# T_STorM32_NT_motor_v42ECg4_000.net
KiCad netlist of a schematic drawn in EAGLE
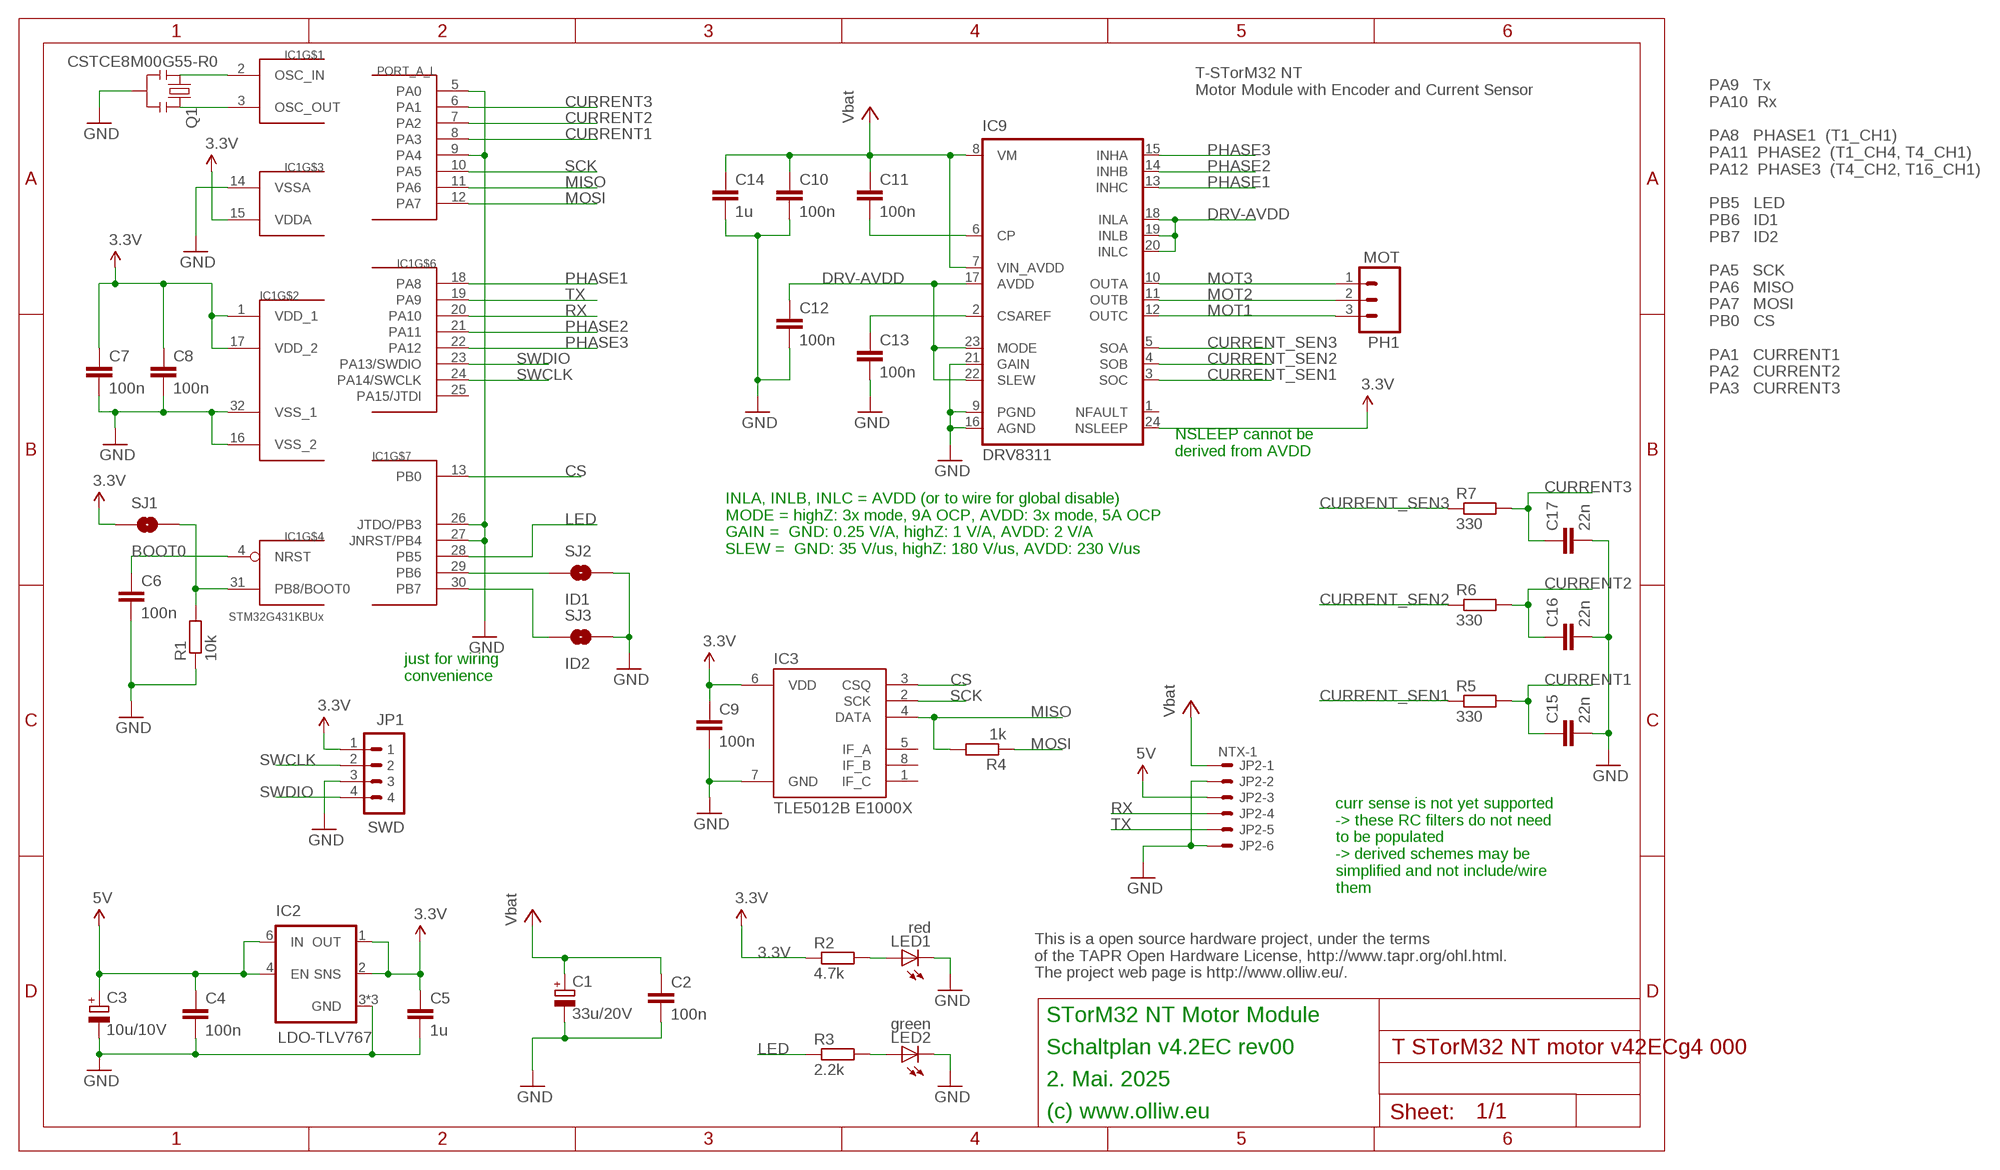
[diagram p0: schematic, sheet 1]

(export (version "E")
  (design (tool "Eeschema 10.0.6"))
  (components
    (comp (ref "C1")
      (value "33u/20V")
      (footprint "eagle-import:SMC_C")
      (libsource (lib "eagle-import") (part "CPOL-EUSMCC"))
    )
    (comp (ref "C2")
      (value "100n")
      (footprint "eagle-import:C0603")
      (libsource (lib "eagle-import") (part "C-EUC0603"))
    )
    (comp (ref "C3")
      (value "10u/10V")
      (footprint "eagle-import:SMC_B")
      (libsource (lib "eagle-import") (part "CPOL-EUSMCB"))
    )
    (comp (ref "C4")
      (value "100n")
      (footprint "eagle-import:C0603")
      (libsource (lib "eagle-import") (part "C-EUC0603"))
    )
    (comp (ref "C5")
      (value "1u")
      (footprint "eagle-import:C0603")
      (libsource (lib "eagle-import") (part "C-EUC0603"))
    )
    (comp (ref "C6")
      (value "100n")
      (footprint "eagle-import:C0402")
      (libsource (lib "eagle-import") (part "C-EUC0402"))
    )
    (comp (ref "C7")
      (value "100n")
      (footprint "eagle-import:C0402")
      (libsource (lib "eagle-import") (part "C-EUC0402"))
    )
    (comp (ref "C8")
      (value "100n")
      (footprint "eagle-import:C0402")
      (libsource (lib "eagle-import") (part "C-EUC0402"))
    )
    (comp (ref "C9")
      (value "100n")
      (footprint "eagle-import:C0402")
      (libsource (lib "eagle-import") (part "C-EUC0402"))
    )
    (comp (ref "C10")
      (value "100n")
      (footprint "eagle-import:C0402")
      (libsource (lib "eagle-import") (part "C-EUC0402"))
    )
    (comp (ref "C11")
      (value "100n")
      (footprint "eagle-import:C0402")
      (libsource (lib "eagle-import") (part "C-EUC0402"))
    )
    (comp (ref "C12")
      (value "100n")
      (footprint "eagle-import:C0402")
      (libsource (lib "eagle-import") (part "C-EUC0402"))
    )
    (comp (ref "C13")
      (value "100n")
      (footprint "eagle-import:C0402")
      (libsource (lib "eagle-import") (part "C-EUC0402"))
    )
    (comp (ref "C14")
      (value "1u")
      (footprint "eagle-import:C0603")
      (libsource (lib "eagle-import") (part "C-EUC0603"))
    )
    (comp (ref "C15")
      (value "22n")
      (footprint "eagle-import:C0402")
      (libsource (lib "eagle-import") (part "C-EUC0402"))
    )
    (comp (ref "C16")
      (value "22n")
      (footprint "eagle-import:C0402")
      (libsource (lib "eagle-import") (part "C-EUC0402"))
    )
    (comp (ref "C17")
      (value "22n")
      (footprint "eagle-import:C0402")
      (libsource (lib "eagle-import") (part "C-EUC0402"))
    )
    (comp (ref "IC1")
      (value "STM32G431KBUx")
      (footprint "eagle-import:UFQFPN32")
      (libsource (lib "eagle-import") (part "STM32G4X1KX"))
    )
    (comp (ref "IC2")
      (value "LDO-TLV767")
      (footprint "eagle-import:WSON-6-2X2")
      (libsource (lib "eagle-import") (part "LDO-TLV767"))
    )
    (comp (ref "IC3")
      (value "TLE5012B E1000X")
      (footprint "eagle-import:SO08")
      (libsource (lib "eagle-import") (part "TLE5012B"))
    )
    (comp (ref "IC9")
      (value "DRV8311")
      (footprint "eagle-import:QFN(WQFN)24-3X3-DRV8311")
      (libsource (lib "eagle-import") (part "DRV8311"))
    )
    (comp (ref "JP1")
      (value "SWD")
      (footprint "eagle-import:4X1_1P27_OCT_BILEX")
      (libsource (lib "eagle-import") (part "P4X1_1P27-OCT_BILEX"))
    )
    (comp (ref "JP2")
      (value "NTX-1")
      (footprint "eagle-import:SM06B-SRSS-TB")
      (libsource (lib "eagle-import") (part "?M06B-SRSS-TBS"))
    )
    (comp (ref "LED1")
      (value "red")
      (footprint "eagle-import:CHIPLED_0603")
      (libsource (lib "eagle-import") (part "LEDCHIPLED_0603"))
    )
    (comp (ref "LED2")
      (value "green")
      (footprint "eagle-import:CHIPLED_0603")
      (libsource (lib "eagle-import") (part "LEDCHIPLED_0603"))
    )
    (comp (ref "PH1")
      (value "MOT")
      (footprint "eagle-import:1X03_NO_SILK")
      (libsource (lib "eagle-import") (part "M031X03_NO_SILK"))
    )
    (comp (ref "Q1")
      (value "CSTCE8M00G55-R0")
      (footprint "eagle-import:RESONATOR-SMD")
      (libsource (lib "eagle-import") (part "RESONATORSMD"))
    )
    (comp (ref "R1")
      (value "10k")
      (footprint "eagle-import:R0402")
      (libsource (lib "eagle-import") (part "R-EU_R0402"))
    )
    (comp (ref "R2")
      (value "4.7k")
      (footprint "eagle-import:R0402")
      (libsource (lib "eagle-import") (part "R-EU_R0402"))
    )
    (comp (ref "R3")
      (value "2.2k")
      (footprint "eagle-import:R0402")
      (libsource (lib "eagle-import") (part "R-EU_R0402"))
    )
    (comp (ref "R4")
      (value "1k")
      (footprint "eagle-import:R0402")
      (libsource (lib "eagle-import") (part "R-EU_R0402"))
    )
    (comp (ref "R5")
      (value "330")
      (footprint "eagle-import:R0402")
      (libsource (lib "eagle-import") (part "R-EU_R0402"))
    )
    (comp (ref "R6")
      (value "330")
      (footprint "eagle-import:R0402")
      (libsource (lib "eagle-import") (part "R-EU_R0402"))
    )
    (comp (ref "R7")
      (value "330")
      (footprint "eagle-import:R0402")
      (libsource (lib "eagle-import") (part "R-EU_R0402"))
    )
    (comp (ref "SJ1")
      (value "BOOT0")
      (footprint "eagle-import:SJ_2S-NO")
      (libsource (lib "eagle-import") (part "SOLDERJUMPERNO"))
    )
    (comp (ref "SJ2")
      (value "ID1")
      (footprint "eagle-import:SJ_2S-NO")
      (libsource (lib "eagle-import") (part "SOLDERJUMPERNO"))
    )
    (comp (ref "SJ3")
      (value "ID2")
      (footprint "eagle-import:SJ_2S-NO")
      (libsource (lib "eagle-import") (part "SOLDERJUMPERNO"))
    )
  )
  (nets
    (net (code "1") (name "/CS") (class "Default")
      (node (ref "IC1") (pin "13") (pinfunction "PB0_13") (pintype "bidirectional"))
      (node (ref "IC3") (pin "3") (pinfunction "CSQ_3") (pintype "input"))
    )
    (net (code "2") (name "/CURRENT1") (class "Default")
      (node (ref "C15") (pin "1") (pinfunction "1_1") (pintype "passive"))
      (node (ref "IC1") (pin "8") (pinfunction "PA3_8") (pintype "bidirectional"))
      (node (ref "R5") (pin "2") (pinfunction "2_2") (pintype "passive"))
    )
    (net (code "3") (name "/CURRENT2") (class "Default")
      (node (ref "C16") (pin "1") (pinfunction "1_1") (pintype "passive"))
      (node (ref "IC1") (pin "7") (pinfunction "PA2_7") (pintype "bidirectional"))
      (node (ref "R6") (pin "2") (pinfunction "2_2") (pintype "passive"))
    )
    (net (code "4") (name "/CURRENT3") (class "Default")
      (node (ref "C17") (pin "1") (pinfunction "1_1") (pintype "passive"))
      (node (ref "IC1") (pin "6") (pinfunction "PA1_6") (pintype "bidirectional"))
      (node (ref "R7") (pin "2") (pinfunction "2_2") (pintype "passive"))
    )
    (net (code "5") (name "/CURRENT_SEN1") (class "Default")
      (node (ref "IC9") (pin "3") (pinfunction "SOC_3") (pintype "output"))
      (node (ref "R5") (pin "1") (pinfunction "1_1") (pintype "passive"))
    )
    (net (code "6") (name "/CURRENT_SEN2") (class "Default")
      (node (ref "IC9") (pin "4") (pinfunction "SOB_4") (pintype "output"))
      (node (ref "R6") (pin "1") (pinfunction "1_1") (pintype "passive"))
    )
    (net (code "7") (name "/CURRENT_SEN3") (class "Default")
      (node (ref "IC9") (pin "5") (pinfunction "SOA_5") (pintype "output"))
      (node (ref "R7") (pin "1") (pinfunction "1_1") (pintype "passive"))
    )
    (net (code "8") (name "/DRV-AVDD") (class "Default")
      (node (ref "C12") (pin "1") (pinfunction "1_1") (pintype "passive"))
      (node (ref "IC9") (pin "17") (pinfunction "AVDD_17") (pintype "power_in"))
      (node (ref "IC9") (pin "18") (pinfunction "INLA_18") (pintype "input"))
      (node (ref "IC9") (pin "19") (pinfunction "INLB_19") (pintype "input"))
      (node (ref "IC9") (pin "20") (pinfunction "INLC_20") (pintype "input"))
      (node (ref "IC9") (pin "22") (pinfunction "SLEW_22") (pintype "input"))
      (node (ref "IC9") (pin "23") (pinfunction "MODE_23") (pintype "input"))
    )
    (net (code "9") (name "/LED") (class "Default")
      (node (ref "IC1") (pin "28") (pinfunction "PB5_28") (pintype "bidirectional"))
      (node (ref "R3") (pin "1") (pinfunction "1_1") (pintype "passive"))
    )
    (net (code "10") (name "/MISO") (class "Default")
      (node (ref "IC1") (pin "11") (pinfunction "PA6_11") (pintype "bidirectional"))
      (node (ref "IC3") (pin "4") (pinfunction "DATA_4") (pintype "bidirectional"))
      (node (ref "R4") (pin "2") (pinfunction "2_2") (pintype "passive"))
    )
    (net (code "11") (name "/MOSI") (class "Default")
      (node (ref "IC1") (pin "12") (pinfunction "PA7_12") (pintype "bidirectional"))
      (node (ref "R4") (pin "1") (pinfunction "1_1") (pintype "passive"))
    )
    (net (code "12") (name "/MOT1") (class "Default")
      (node (ref "IC9") (pin "12") (pinfunction "OUTC_12") (pintype "output"))
      (node (ref "PH1") (pin "3") (pinfunction "3_3") (pintype "passive"))
    )
    (net (code "13") (name "/MOT2") (class "Default")
      (node (ref "IC9") (pin "11") (pinfunction "OUTB_11") (pintype "output"))
      (node (ref "PH1") (pin "2") (pinfunction "2_2") (pintype "passive"))
    )
    (net (code "14") (name "/MOT3") (class "Default")
      (node (ref "IC9") (pin "10") (pinfunction "OUTA_10") (pintype "output"))
      (node (ref "PH1") (pin "1") (pinfunction "1_1") (pintype "passive"))
    )
    (net (code "15") (name "/PHASE1") (class "Default")
      (node (ref "IC1") (pin "18") (pinfunction "PA8_18") (pintype "bidirectional"))
      (node (ref "IC9") (pin "13") (pinfunction "INHC_13") (pintype "input"))
    )
    (net (code "16") (name "/PHASE2") (class "Default")
      (node (ref "IC1") (pin "21") (pinfunction "PA11_21") (pintype "bidirectional"))
      (node (ref "IC9") (pin "14") (pinfunction "INHB_14") (pintype "input"))
    )
    (net (code "17") (name "/PHASE3") (class "Default")
      (node (ref "IC1") (pin "22") (pinfunction "PA12_22") (pintype "bidirectional"))
      (node (ref "IC9") (pin "15") (pinfunction "INHA_15") (pintype "input"))
    )
    (net (code "18") (name "/RX") (class "Default")
      (node (ref "IC1") (pin "20") (pinfunction "PA10_20") (pintype "bidirectional"))
      (node (ref "JP2") (pin "4") (pinfunction "S_4") (pintype "passive"))
    )
    (net (code "19") (name "/SCK") (class "Default")
      (node (ref "IC1") (pin "10") (pinfunction "PA5_10") (pintype "bidirectional"))
      (node (ref "IC3") (pin "2") (pinfunction "SCK_2") (pintype "input"))
    )
    (net (code "20") (name "/SWCLK") (class "Default")
      (node (ref "IC1") (pin "24") (pinfunction "PA14/SWCLK_24") (pintype "bidirectional"))
      (node (ref "JP1") (pin "2") (pinfunction "2_2") (pintype "passive"))
    )
    (net (code "21") (name "/SWDIO") (class "Default")
      (node (ref "IC1") (pin "23") (pinfunction "PA13/SWDIO_23") (pintype "bidirectional"))
      (node (ref "JP1") (pin "4") (pinfunction "4_4") (pintype "passive"))
    )
    (net (code "22") (name "/TX") (class "Default")
      (node (ref "IC1") (pin "19") (pinfunction "PA9_19") (pintype "bidirectional"))
      (node (ref "JP2") (pin "5") (pinfunction "S_5") (pintype "passive"))
    )
    (net (code "23") (name "3.3V") (class "Default")
      (node (ref "C5") (pin "1") (pinfunction "1_1") (pintype "passive"))
      (node (ref "C7") (pin "1") (pinfunction "1_1") (pintype "passive"))
      (node (ref "C8") (pin "1") (pinfunction "1_1") (pintype "passive"))
      (node (ref "C9") (pin "1") (pinfunction "1_1") (pintype "passive"))
      (node (ref "IC1") (pin "1") (pinfunction "VDD_1_1") (pintype "power_in"))
      (node (ref "IC1") (pin "15") (pinfunction "VDDA_15") (pintype "power_in"))
      (node (ref "IC1") (pin "17") (pinfunction "VDD_2_17") (pintype "power_in"))
      (node (ref "IC2") (pin "1") (pinfunction "OUT_1") (pintype "output"))
      (node (ref "IC2") (pin "2") (pinfunction "SNS_2") (pintype "input"))
      (node (ref "IC3") (pin "6") (pinfunction "VDD_6") (pintype "power_in"))
      (node (ref "IC9") (pin "24") (pinfunction "NSLEEP_24") (pintype "input"))
      (node (ref "JP1") (pin "1") (pinfunction "1_1") (pintype "passive"))
      (node (ref "R2") (pin "1") (pinfunction "1_1") (pintype "passive"))
      (node (ref "SJ1") (pin "1") (pinfunction "1_1") (pintype "passive"))
    )
    (net (code "24") (name "5V") (class "Default")
      (node (ref "C3") (pin "+") (pinfunction "+_+") (pintype "passive"))
      (node (ref "C4") (pin "1") (pinfunction "1_1") (pintype "passive"))
      (node (ref "IC2") (pin "4") (pinfunction "EN_4") (pintype "input"))
      (node (ref "IC2") (pin "6") (pinfunction "IN_6") (pintype "power_in"))
      (node (ref "JP2") (pin "3") (pinfunction "S_3") (pintype "passive"))
    )
    (net (code "25") (name "GND") (class "Default")
      (node (ref "C1") (pin "-") (pinfunction "-_-") (pintype "passive"))
      (node (ref "C10") (pin "2") (pinfunction "2_2") (pintype "passive"))
      (node (ref "C12") (pin "2") (pinfunction "2_2") (pintype "passive"))
      (node (ref "C13") (pin "2") (pinfunction "2_2") (pintype "passive"))
      (node (ref "C14") (pin "2") (pinfunction "2_2") (pintype "passive"))
      (node (ref "C15") (pin "2") (pinfunction "2_2") (pintype "passive"))
      (node (ref "C16") (pin "2") (pinfunction "2_2") (pintype "passive"))
      (node (ref "C17") (pin "2") (pinfunction "2_2") (pintype "passive"))
      (node (ref "C2") (pin "2") (pinfunction "2_2") (pintype "passive"))
      (node (ref "C3") (pin "-") (pinfunction "-_-") (pintype "passive"))
      (node (ref "C4") (pin "2") (pinfunction "2_2") (pintype "passive"))
      (node (ref "C5") (pin "2") (pinfunction "2_2") (pintype "passive"))
      (node (ref "C6") (pin "2") (pinfunction "2_2") (pintype "passive"))
      (node (ref "C7") (pin "2") (pinfunction "2_2") (pintype "passive"))
      (node (ref "C8") (pin "2") (pinfunction "2_2") (pintype "passive"))
      (node (ref "C9") (pin "2") (pinfunction "2_2") (pintype "passive"))
      (node (ref "IC1") (pin "14") (pinfunction "VSSA_14") (pintype "power_in"))
      (node (ref "IC1") (pin "16") (pinfunction "VSS_2_16") (pintype "power_in"))
      (node (ref "IC1") (pin "26") (pinfunction "JTDO/PB3_26") (pintype "bidirectional"))
      (node (ref "IC1") (pin "27") (pinfunction "JNRST/PB4_27") (pintype "bidirectional"))
      (node (ref "IC1") (pin "32") (pinfunction "VSS_1_32") (pintype "power_in"))
      (node (ref "IC1") (pin "5") (pinfunction "PA0_5") (pintype "bidirectional"))
      (node (ref "IC1") (pin "9") (pinfunction "PA4_9") (pintype "bidirectional"))
      (node (ref "IC2") (pin "3") (pinfunction "GND_3") (pintype "power_in"))
      (node (ref "IC2") (pin "5") (pinfunction "GND_5") (pintype "power_in"))
      (node (ref "IC2") (pin "7") (pinfunction "GND_7") (pintype "power_in"))
      (node (ref "IC3") (pin "7") (pinfunction "GND_7") (pintype "power_in"))
      (node (ref "IC9") (pin "16") (pinfunction "AGND_16") (pintype "power_in"))
      (node (ref "IC9") (pin "21") (pinfunction "GAIN_21") (pintype "input"))
      (node (ref "IC9") (pin "9") (pinfunction "PGND_9") (pintype "power_in"))
      (node (ref "JP1") (pin "3") (pinfunction "3_3") (pintype "passive"))
      (node (ref "JP2") (pin "2") (pinfunction "S_2") (pintype "passive"))
      (node (ref "JP2") (pin "6") (pinfunction "S_6") (pintype "passive"))
      (node (ref "LED1") (pin "C") (pinfunction "C_C") (pintype "passive"))
      (node (ref "LED2") (pin "C") (pinfunction "C_C") (pintype "passive"))
      (node (ref "Q1") (pin "2") (pinfunction "2_2") (pintype "passive"))
      (node (ref "R1") (pin "1") (pinfunction "1_1") (pintype "passive"))
      (node (ref "SJ2") (pin "2") (pinfunction "2_2") (pintype "passive"))
      (node (ref "SJ3") (pin "2") (pinfunction "2_2") (pintype "passive"))
    )
    (net (code "26") (name "Net-(IC1A-OSC_IN)") (class "Default")
      (node (ref "IC1") (pin "2") (pinfunction "OSC_IN_2") (pintype "input"))
      (node (ref "Q1") (pin "1") (pinfunction "1_1") (pintype "passive"))
    )
    (net (code "27") (name "Net-(IC1A-OSC_OUT)") (class "Default")
      (node (ref "IC1") (pin "3") (pinfunction "OSC_OUT_3") (pintype "output"))
      (node (ref "Q1") (pin "3") (pinfunction "3_3") (pintype "passive"))
    )
    (net (code "28") (name "Net-(IC1D-NRST)") (class "Default")
      (node (ref "C6") (pin "1") (pinfunction "1_1") (pintype "passive"))
      (node (ref "IC1") (pin "4") (pinfunction "NRST_4") (pintype "input"))
    )
    (net (code "29") (name "Net-(IC1D-PB8{slash}BOOT0)") (class "Default")
      (node (ref "IC1") (pin "31") (pinfunction "PB8/BOOT0_31") (pintype "input"))
      (node (ref "R1") (pin "2") (pinfunction "2_2") (pintype "passive"))
      (node (ref "SJ1") (pin "2") (pinfunction "2_2") (pintype "passive"))
    )
    (net (code "30") (name "Net-(IC1G-PB6)") (class "Default")
      (node (ref "IC1") (pin "29") (pinfunction "PB6_29") (pintype "bidirectional"))
      (node (ref "SJ2") (pin "1") (pinfunction "1_1") (pintype "passive"))
    )
    (net (code "31") (name "Net-(IC1G-PB7)") (class "Default")
      (node (ref "IC1") (pin "30") (pinfunction "PB7_30") (pintype "bidirectional"))
      (node (ref "SJ3") (pin "1") (pinfunction "1_1") (pintype "passive"))
    )
    (net (code "32") (name "Net-(IC9-CP)") (class "Default")
      (node (ref "C11") (pin "2") (pinfunction "2_2") (pintype "passive"))
      (node (ref "IC9") (pin "6") (pinfunction "CP_6") (pintype "power_in"))
    )
    (net (code "33") (name "Net-(IC9-CSAREF)") (class "Default")
      (node (ref "C13") (pin "1") (pinfunction "1_1") (pintype "passive"))
      (node (ref "IC9") (pin "2") (pinfunction "CSAREF_2") (pintype "power_in"))
    )
    (net (code "34") (name "Net-(LED1-PadA)") (class "Default")
      (node (ref "LED1") (pin "A") (pinfunction "A_A") (pintype "passive"))
      (node (ref "R2") (pin "2") (pinfunction "2_2") (pintype "passive"))
    )
    (net (code "35") (name "Net-(LED2-PadA)") (class "Default")
      (node (ref "LED2") (pin "A") (pinfunction "A_A") (pintype "passive"))
      (node (ref "R3") (pin "2") (pinfunction "2_2") (pintype "passive"))
    )
    (net (code "36") (name "Vbat") (class "Default")
      (node (ref "C1") (pin "+") (pinfunction "+_+") (pintype "passive"))
      (node (ref "C10") (pin "1") (pinfunction "1_1") (pintype "passive"))
      (node (ref "C11") (pin "1") (pinfunction "1_1") (pintype "passive"))
      (node (ref "C14") (pin "1") (pinfunction "1_1") (pintype "passive"))
      (node (ref "C2") (pin "1") (pinfunction "1_1") (pintype "passive"))
      (node (ref "IC9") (pin "7") (pinfunction "VIN_AVDD_7") (pintype "power_in"))
      (node (ref "IC9") (pin "8") (pinfunction "VM_8") (pintype "power_in"))
      (node (ref "JP2") (pin "1") (pinfunction "S_1") (pintype "passive"))
    )
    (net (code "37") (name "unconnected-(IC1F-PA15{slash}JTDI-Pad25)") (class "Default")
      (node (ref "IC1") (pin "25") (pinfunction "PA15/JTDI_25") (pintype "bidirectional"))
    )
    (net (code "38") (name "unconnected-(IC3-IF_A-Pad5)") (class "Default")
      (node (ref "IC3") (pin "5") (pinfunction "IF_A_5") (pintype "bidirectional"))
    )
    (net (code "39") (name "unconnected-(IC3-IF_B-Pad8)") (class "Default")
      (node (ref "IC3") (pin "8") (pinfunction "IF_B_8") (pintype "output"))
    )
    (net (code "40") (name "unconnected-(IC3-IF_C-Pad1)") (class "Default")
      (node (ref "IC3") (pin "1") (pinfunction "IF_C_1") (pintype "bidirectional"))
    )
    (net (code "41") (name "unconnected-(IC9-NFAULT-Pad1)") (class "Default")
      (node (ref "IC9") (pin "1") (pinfunction "NFAULT_1") (pintype "output"))
    )
  )
)
